# perfect-cell-v0_1.net
KiCad netlist of a schematic drawn in EAGLE
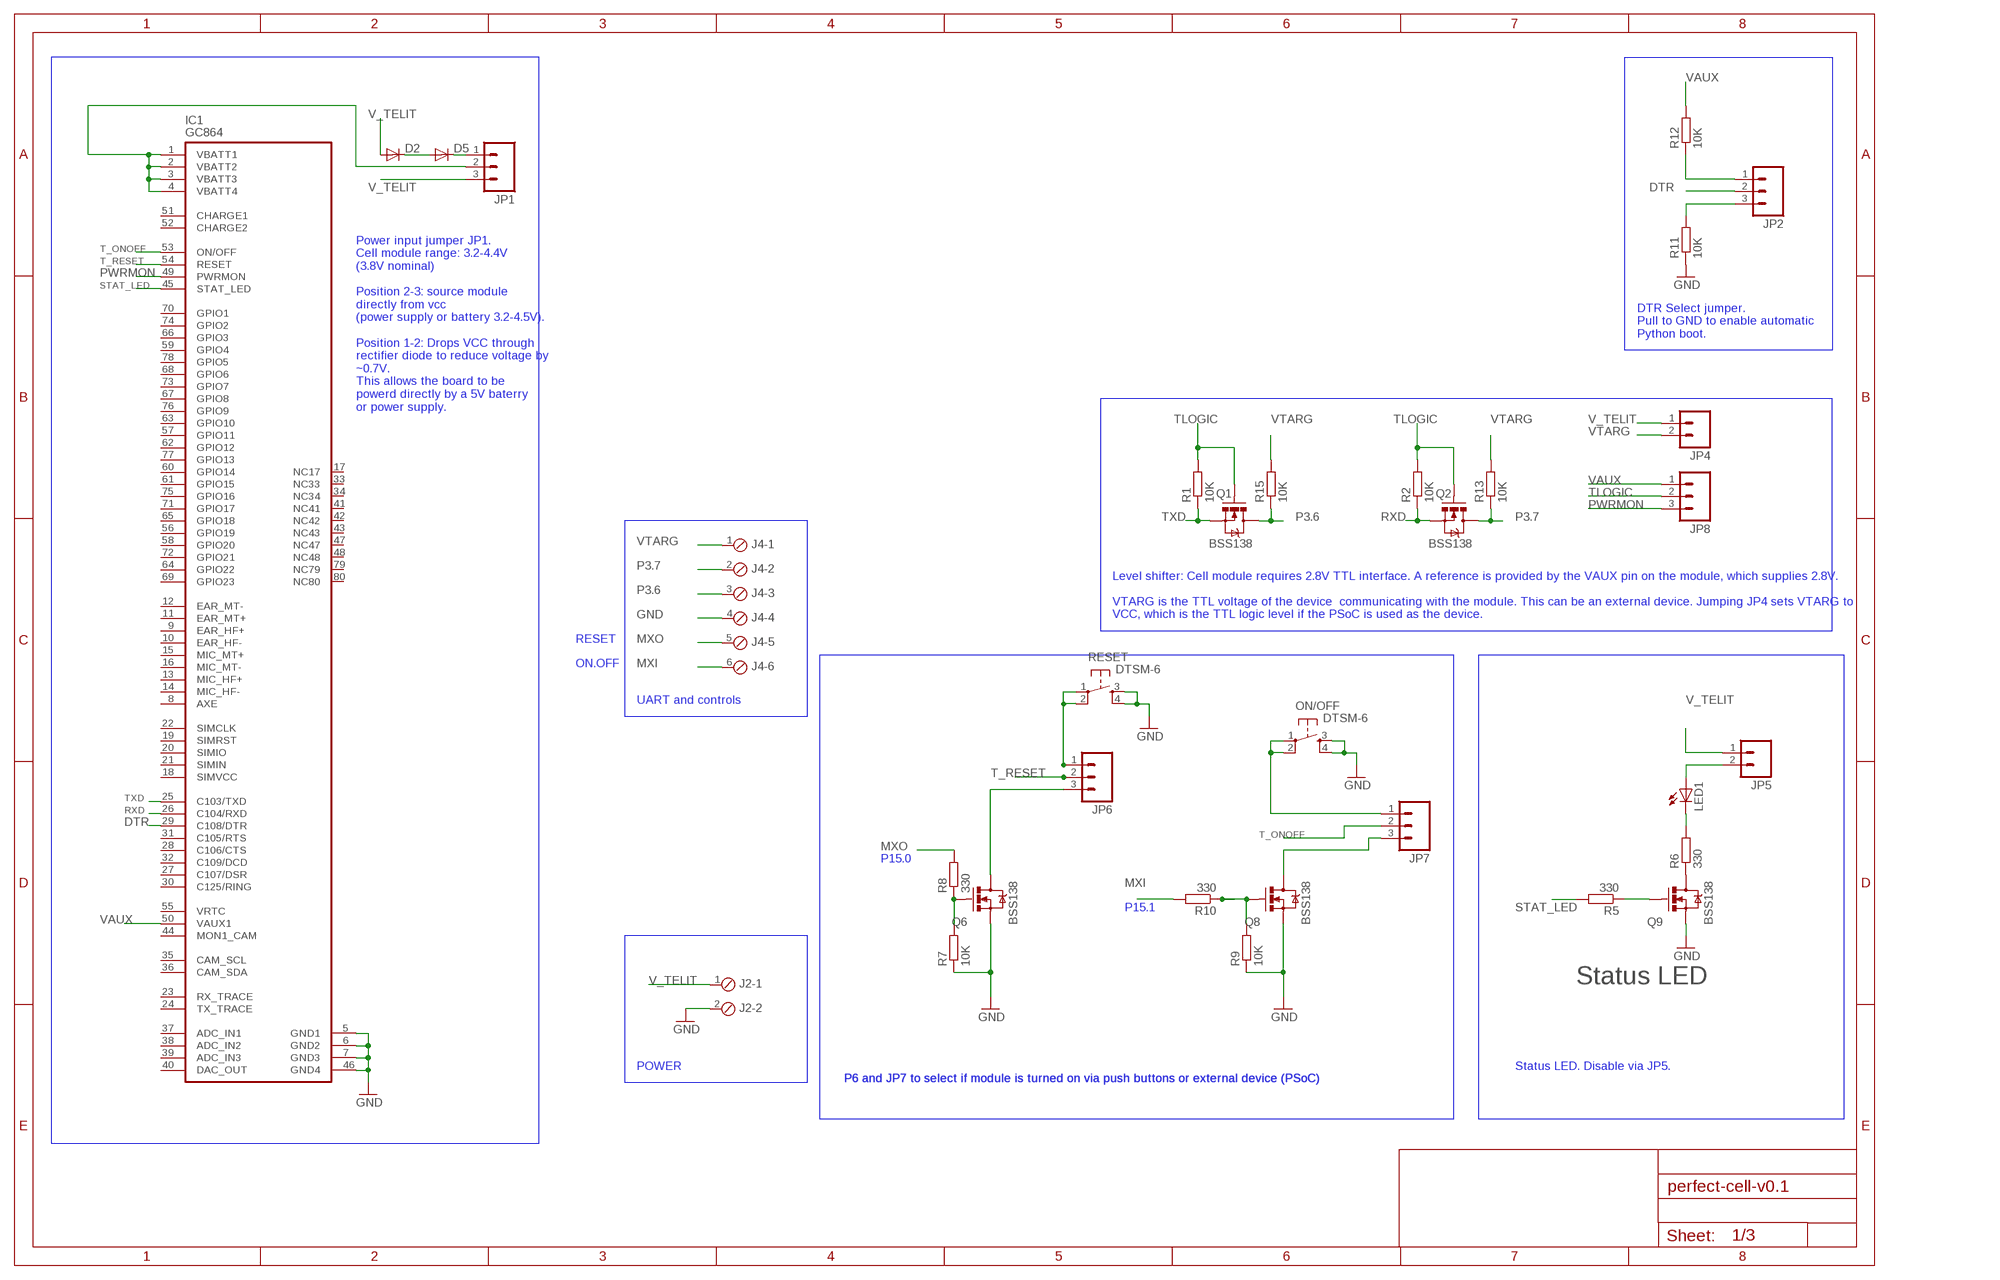
[diagram p0: schematic, sheet 1]
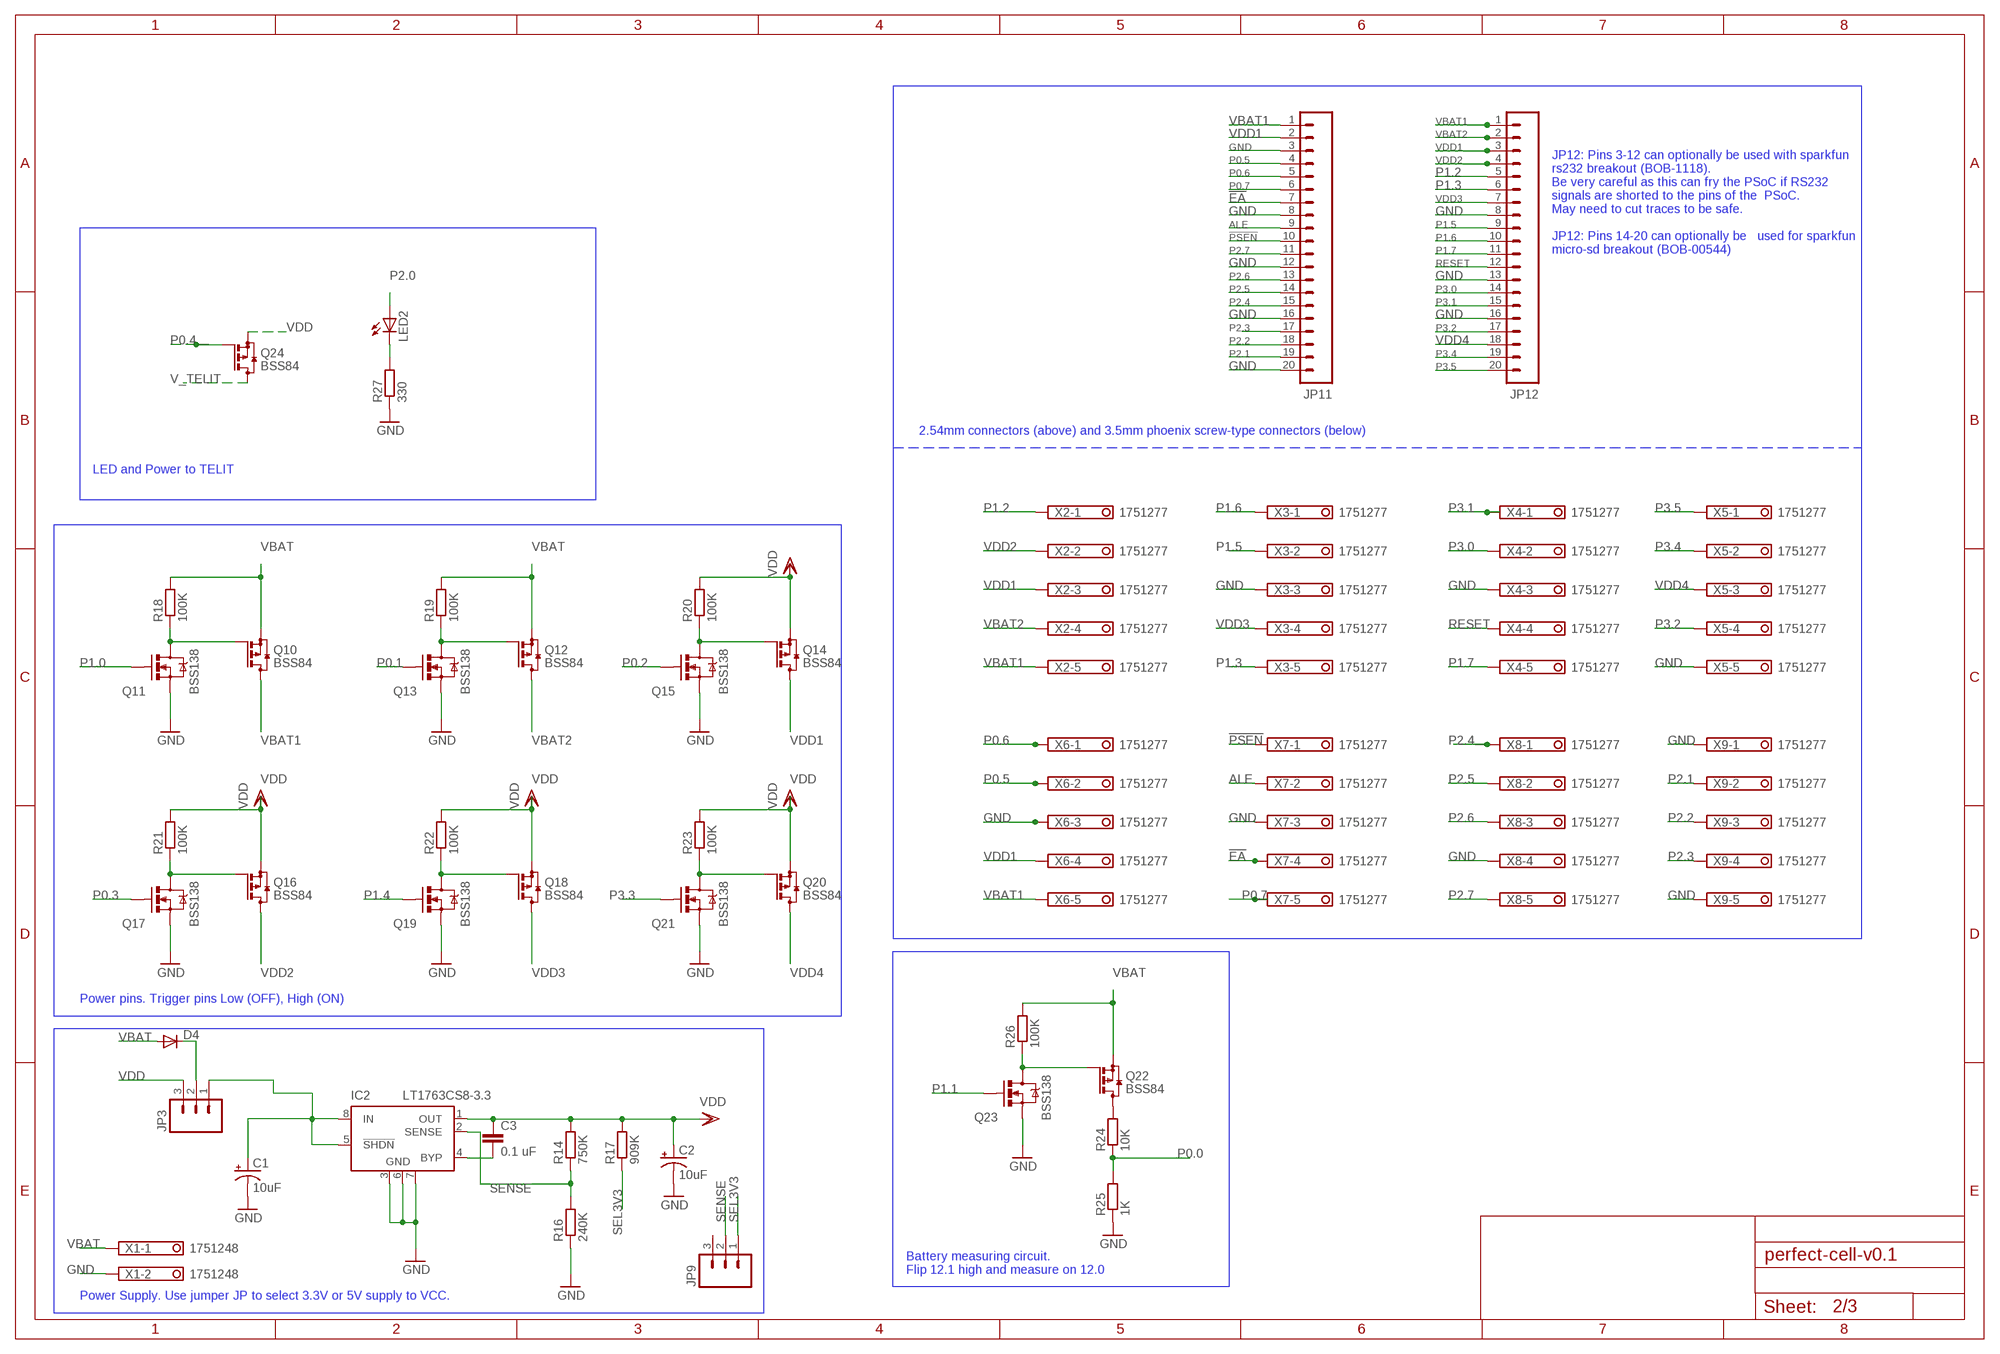
[diagram p1: schematic, sheet 2]
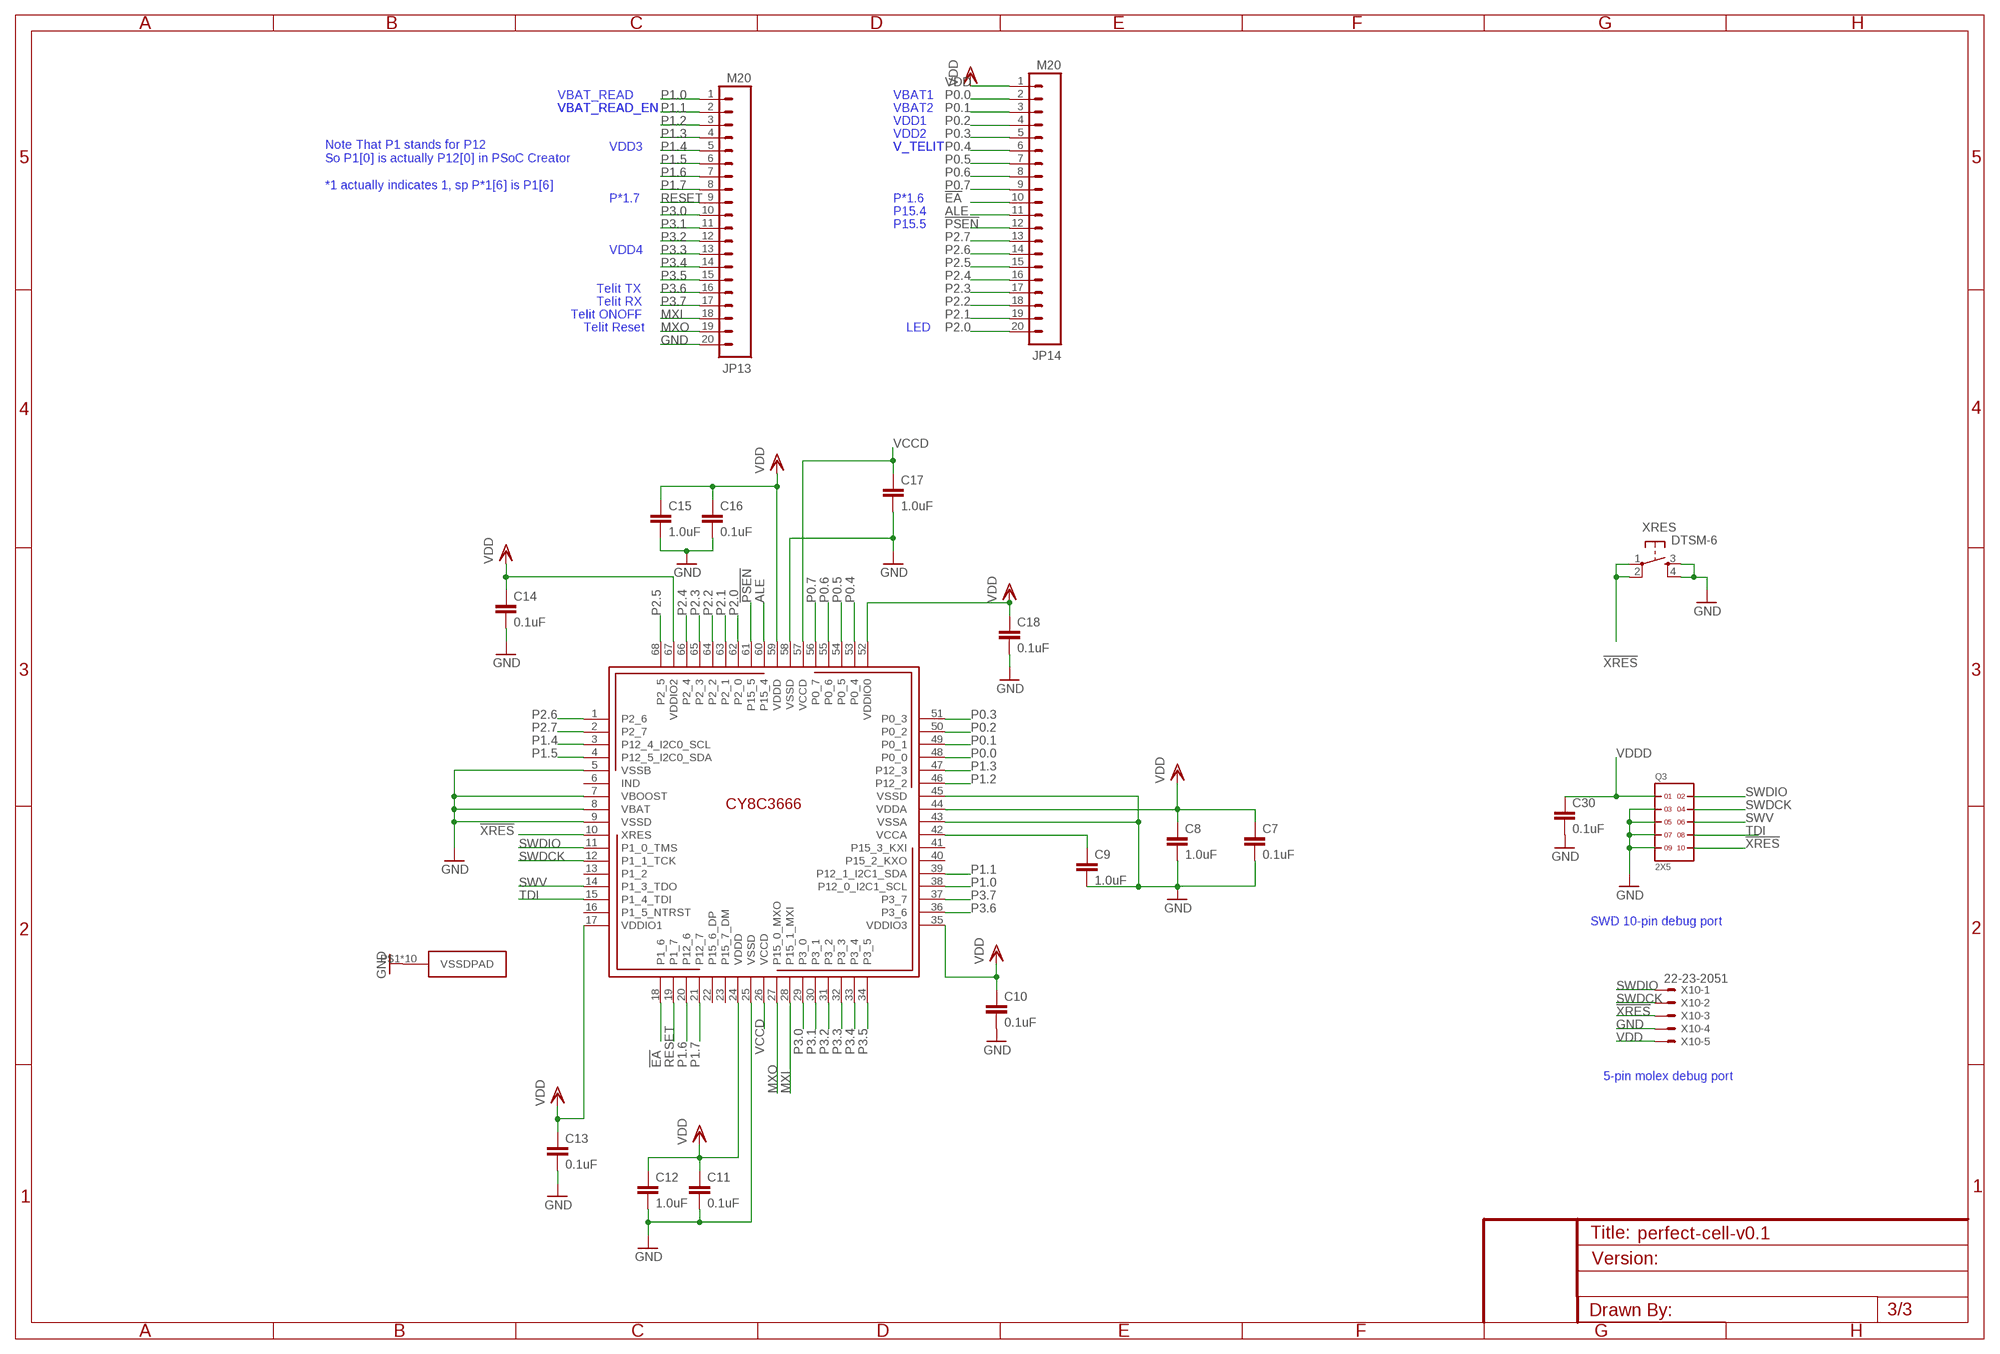
[diagram p2: schematic, sheet 3]

(export (version "E")
  (design (tool "Eeschema 10.0.6"))
  (components
    (comp (ref "C1")
      (value "10uF")
      (footprint "eagle-import:EIA3216")
      (libsource (lib "eagle-import") (part "10UF-16V-10%(TANT)"))
    )
    (comp (ref "C2")
      (value "10uF")
      (footprint "eagle-import:EIA3216")
      (libsource (lib "eagle-import") (part "10UF-16V-10%(TANT)"))
    )
    (comp (ref "C3")
      (value "0.1 uF")
      (footprint "eagle-import:0402-CAP")
      (libsource (lib "eagle-import") (part "CAP0402-CAP"))
    )
    (comp (ref "D4")
      (value "DIODESMA")
      (footprint "eagle-import:SMA-DIODE")
      (libsource (lib "eagle-import") (part "DIODESMA"))
    )
    (comp (ref "IC2")
      (value "LT1763CS8-3.3")
      (footprint "eagle-import:SOIC8")
      (libsource (lib "eagle-import") (part "LT1763CS8-3.3"))
    )
    (comp (ref "JP3")
      (value "M03LOCK")
      (footprint "eagle-import:1X03_LOCK")
      (libsource (lib "eagle-import") (part "M03LOCK"))
    )
    (comp (ref "JP9")
      (value "M03LOCK")
      (footprint "eagle-import:1X03_LOCK")
      (libsource (lib "eagle-import") (part "M03LOCK"))
    )
    (comp (ref "JP11")
      (value "M20")
      (footprint "eagle-import:1X20")
      (libsource (lib "eagle-import") (part "SparkFun-Connectors_M20"))
    )
    (comp (ref "JP12")
      (value "M20")
      (footprint "eagle-import:1X20")
      (libsource (lib "eagle-import") (part "SparkFun-Connectors_M20"))
    )
    (comp (ref "LED2")
      (value "LEDSML0805")
      (footprint "eagle-import:SML0805")
      (libsource (lib "eagle-import") (part "LEDSML0805"))
    )
    (comp (ref "Q10")
      (value "BSS84")
      (footprint "eagle-import:SOT23")
      (libsource (lib "eagle-import") (part "BSS84"))
    )
    (comp (ref "Q11")
      (value "BSS138")
      (footprint "eagle-import:SOT23-3")
      (libsource (lib "eagle-import") (part "MOSFET-NCHANNELSMD"))
    )
    (comp (ref "Q12")
      (value "BSS84")
      (footprint "eagle-import:SOT23")
      (libsource (lib "eagle-import") (part "BSS84"))
    )
    (comp (ref "Q13")
      (value "BSS138")
      (footprint "eagle-import:SOT23-3")
      (libsource (lib "eagle-import") (part "MOSFET-NCHANNELSMD"))
    )
    (comp (ref "Q14")
      (value "BSS84")
      (footprint "eagle-import:SOT23")
      (libsource (lib "eagle-import") (part "BSS84"))
    )
    (comp (ref "Q15")
      (value "BSS138")
      (footprint "eagle-import:SOT23-3")
      (libsource (lib "eagle-import") (part "MOSFET-NCHANNELSMD"))
    )
    (comp (ref "Q16")
      (value "BSS84")
      (footprint "eagle-import:SOT23")
      (libsource (lib "eagle-import") (part "BSS84"))
    )
    (comp (ref "Q17")
      (value "BSS138")
      (footprint "eagle-import:SOT23-3")
      (libsource (lib "eagle-import") (part "MOSFET-NCHANNELSMD"))
    )
    (comp (ref "Q18")
      (value "BSS84")
      (footprint "eagle-import:SOT23")
      (libsource (lib "eagle-import") (part "BSS84"))
    )
    (comp (ref "Q19")
      (value "BSS138")
      (footprint "eagle-import:SOT23-3")
      (libsource (lib "eagle-import") (part "MOSFET-NCHANNELSMD"))
    )
    (comp (ref "Q20")
      (value "BSS84")
      (footprint "eagle-import:SOT23")
      (libsource (lib "eagle-import") (part "BSS84"))
    )
    (comp (ref "Q21")
      (value "BSS138")
      (footprint "eagle-import:SOT23-3")
      (libsource (lib "eagle-import") (part "MOSFET-NCHANNELSMD"))
    )
    (comp (ref "Q22")
      (value "BSS84")
      (footprint "eagle-import:SOT23")
      (libsource (lib "eagle-import") (part "BSS84"))
    )
    (comp (ref "Q23")
      (value "BSS138")
      (footprint "eagle-import:SOT23-3")
      (libsource (lib "eagle-import") (part "MOSFET-NCHANNELSMD"))
    )
    (comp (ref "Q24")
      (value "BSS84")
      (footprint "eagle-import:SOT23")
      (libsource (lib "eagle-import") (part "BSS84"))
    )
    (comp (ref "R14")
      (value "750K")
      (footprint "eagle-import:R0805")
      (libsource (lib "eagle-import") (part "R-EU_R0805"))
    )
    (comp (ref "R16")
      (value "240K")
      (footprint "eagle-import:R0805")
      (libsource (lib "eagle-import") (part "R-EU_R0805"))
    )
    (comp (ref "R17")
      (value "909K")
      (footprint "eagle-import:R0805")
      (libsource (lib "eagle-import") (part "R-EU_R0805"))
    )
    (comp (ref "R18")
      (value "100K")
      (footprint "eagle-import:R0805")
      (libsource (lib "eagle-import") (part "R-EU_R0805"))
    )
    (comp (ref "R19")
      (value "100K")
      (footprint "eagle-import:R0805")
      (libsource (lib "eagle-import") (part "R-EU_R0805"))
    )
    (comp (ref "R20")
      (value "100K")
      (footprint "eagle-import:R0805")
      (libsource (lib "eagle-import") (part "R-EU_R0805"))
    )
    (comp (ref "R21")
      (value "100K")
      (footprint "eagle-import:R0805")
      (libsource (lib "eagle-import") (part "R-EU_R0805"))
    )
    (comp (ref "R22")
      (value "100K")
      (footprint "eagle-import:R0805")
      (libsource (lib "eagle-import") (part "R-EU_R0805"))
    )
    (comp (ref "R23")
      (value "100K")
      (footprint "eagle-import:R0805")
      (libsource (lib "eagle-import") (part "R-EU_R0805"))
    )
    (comp (ref "R24")
      (value "10K")
      (footprint "eagle-import:R0805")
      (libsource (lib "eagle-import") (part "R-EU_R0805"))
    )
    (comp (ref "R25")
      (value "1K")
      (footprint "eagle-import:R0805")
      (libsource (lib "eagle-import") (part "R-EU_R0805"))
    )
    (comp (ref "R26")
      (value "100K")
      (footprint "eagle-import:R0805")
      (libsource (lib "eagle-import") (part "R-EU_R0805"))
    )
    (comp (ref "R27")
      (value "330")
      (footprint "eagle-import:R0805")
      (libsource (lib "eagle-import") (part "R-EU_R0805"))
    )
    (comp (ref "X1")
      (value "1751248")
      (footprint "eagle-import:1751248")
      (libsource (lib "eagle-import") (part "1751248"))
    )
    (comp (ref "X2")
      (value "1751277")
      (footprint "eagle-import:1751277")
      (libsource (lib "eagle-import") (part "1751277"))
    )
    (comp (ref "X3")
      (value "1751277")
      (footprint "eagle-import:1751277")
      (libsource (lib "eagle-import") (part "1751277"))
    )
    (comp (ref "X4")
      (value "1751277")
      (footprint "eagle-import:1751277")
      (libsource (lib "eagle-import") (part "1751277"))
    )
    (comp (ref "X5")
      (value "1751277")
      (footprint "eagle-import:1751277")
      (libsource (lib "eagle-import") (part "1751277"))
    )
    (comp (ref "X6")
      (value "1751277")
      (footprint "eagle-import:1751277")
      (libsource (lib "eagle-import") (part "1751277"))
    )
    (comp (ref "X7")
      (value "1751277")
      (footprint "eagle-import:1751277")
      (libsource (lib "eagle-import") (part "1751277"))
    )
    (comp (ref "X8")
      (value "1751277")
      (footprint "eagle-import:1751277")
      (libsource (lib "eagle-import") (part "1751277"))
    )
    (comp (ref "X9")
      (value "1751277")
      (footprint "eagle-import:1751277")
      (libsource (lib "eagle-import") (part "1751277"))
    )
    (comp (ref "C7")
      (value "0.1uF")
      (footprint "eagle-import:0402-CAP")
      (libsource (lib "eagle-import") (part "CAP0402-CAP"))
    )
    (comp (ref "C8")
      (value "1.0uF")
      (footprint "eagle-import:0402-CAP")
      (libsource (lib "eagle-import") (part "CAP0402-CAP"))
    )
    (comp (ref "C9")
      (value "1.0uF")
      (footprint "eagle-import:0402-CAP")
      (libsource (lib "eagle-import") (part "CAP0402-CAP"))
    )
    (comp (ref "C10")
      (value "0.1uF")
      (footprint "eagle-import:0402-CAP")
      (libsource (lib "eagle-import") (part "CAP0402-CAP"))
    )
    (comp (ref "C11")
      (value "0.1uF")
      (footprint "eagle-import:0402-CAP")
      (libsource (lib "eagle-import") (part "CAP0402-CAP"))
    )
    (comp (ref "C12")
      (value "1.0uF")
      (footprint "eagle-import:0402-CAP")
      (libsource (lib "eagle-import") (part "CAP0402-CAP"))
    )
    (comp (ref "C13")
      (value "0.1uF")
      (footprint "eagle-import:0402-CAP")
      (libsource (lib "eagle-import") (part "CAP0402-CAP"))
    )
    (comp (ref "C14")
      (value "0.1uF")
      (footprint "eagle-import:0402-CAP")
      (libsource (lib "eagle-import") (part "CAP0402-CAP"))
    )
    (comp (ref "C15")
      (value "1.0uF")
      (footprint "eagle-import:0402-CAP")
      (libsource (lib "eagle-import") (part "CAP0402-CAP"))
    )
    (comp (ref "C16")
      (value "0.1uF")
      (footprint "eagle-import:0402-CAP")
      (libsource (lib "eagle-import") (part "CAP0402-CAP"))
    )
    (comp (ref "C17")
      (value "1.0uF")
      (footprint "eagle-import:0402-CAP")
      (libsource (lib "eagle-import") (part "CAP0402-CAP"))
    )
    (comp (ref "C18")
      (value "0.1uF")
      (footprint "eagle-import:0402-CAP")
      (libsource (lib "eagle-import") (part "CAP0402-CAP"))
    )
    (comp (ref "C30")
      (value "0.1uF")
      (footprint "eagle-import:0402-CAP")
      (libsource (lib "eagle-import") (part "CAP0402-CAP"))
    )
    (comp (ref "JP13")
      (value "M20")
      (footprint "eagle-import:1X20")
      (libsource (lib "eagle-import") (part "M20"))
    )
    (comp (ref "JP14")
      (value "M20")
      (footprint "eagle-import:1X20")
      (libsource (lib "eagle-import") (part "M20"))
    )
    (comp (ref "Q3")
      (value "2X5")
      (footprint "eagle-import:FTSH-105-01-XXX-DV-K")
      (libsource (lib "eagle-import") (part "2X5"))
    )
    (comp (ref "U$1")
      (value "CY8C3X66LTI")
      (footprint "eagle-import:QFN-68")
      (fields (field (name "PN") "CY8C5568LTI-114"))
      (libsource (lib "eagle-import") (part "CY8C3X66LTI"))
    )
    (comp (ref "X10")
      (value "22-23-2051")
      (footprint "eagle-import:22-23-2051")
      (fields (field (name "MF") "MOLEX"))
      (libsource (lib "eagle-import") (part "22-23-2051"))
    )
    (comp (ref "XRES")
      (value "DTSM-6")
      (footprint "eagle-import:DTSM-6")
      (libsource (lib "eagle-import") (part "DTSM-6"))
    )
    (comp (ref "D2")
      (value "DIODESMA")
      (footprint "eagle-import:SMA-DIODE")
      (libsource (lib "eagle-import") (part "DIODESMA"))
    )
    (comp (ref "D5")
      (value "DIODESMA")
      (footprint "eagle-import:SMA-DIODE")
      (libsource (lib "eagle-import") (part "DIODESMA"))
    )
    (comp (ref "IC1")
      (value "GC864")
      (footprint "eagle-import:GC864")
      (libsource (lib "eagle-import") (part "GC864"))
    )
    (comp (ref "J2")
      (value "MPT2")
      (footprint "eagle-import:2POL254")
      (libsource (lib "eagle-import") (part "MPT2"))
    )
    (comp (ref "J4")
      (value "MPT6")
      (footprint "eagle-import:6POL254")
      (libsource (lib "eagle-import") (part "MPT6"))
    )
    (comp (ref "JP1")
      (value "M03LOCK")
      (footprint "eagle-import:1X03_LOCK")
      (libsource (lib "eagle-import") (part "M03LOCK"))
    )
    (comp (ref "JP2")
      (value "M03LOCK")
      (footprint "eagle-import:1X03_LOCK")
      (libsource (lib "eagle-import") (part "M03LOCK"))
    )
    (comp (ref "JP4")
      (value "M02LOCK")
      (footprint "eagle-import:1X02_LOCK")
      (libsource (lib "eagle-import") (part "M02LOCK"))
    )
    (comp (ref "JP5")
      (value "M02LOCK")
      (footprint "eagle-import:1X02_LOCK")
      (libsource (lib "eagle-import") (part "M02LOCK"))
    )
    (comp (ref "JP6")
      (value "M03LOCK")
      (footprint "eagle-import:1X03_LOCK")
      (libsource (lib "eagle-import") (part "M03LOCK"))
    )
    (comp (ref "JP7")
      (value "M03LOCK")
      (footprint "eagle-import:1X03_LOCK")
      (libsource (lib "eagle-import") (part "M03LOCK"))
    )
    (comp (ref "JP8")
      (value "M03LOCK")
      (footprint "eagle-import:1X03_LOCK")
      (libsource (lib "eagle-import") (part "M03LOCK"))
    )
    (comp (ref "LED1")
      (value "LEDSML0805")
      (footprint "eagle-import:SML0805")
      (libsource (lib "eagle-import") (part "LEDSML0805"))
    )
    (comp (ref "ON/OFF")
      (value "DTSM-6")
      (footprint "eagle-import:DTSM-6")
      (libsource (lib "eagle-import") (part "DTSM-6"))
    )
    (comp (ref "Q1")
      (value "BSS138")
      (footprint "eagle-import:SOT23-3")
      (libsource (lib "eagle-import") (part "MOSFET-NCHANNELSMD"))
    )
    (comp (ref "Q2")
      (value "BSS138")
      (footprint "eagle-import:SOT23-3")
      (libsource (lib "eagle-import") (part "MOSFET-NCHANNELSMD"))
    )
    (comp (ref "Q6")
      (value "BSS138")
      (footprint "eagle-import:SOT23-3")
      (libsource (lib "eagle-import") (part "MOSFET-NCHANNELSMD"))
    )
    (comp (ref "Q8")
      (value "BSS138")
      (footprint "eagle-import:SOT23-3")
      (libsource (lib "eagle-import") (part "MOSFET-NCHANNELSMD"))
    )
    (comp (ref "Q9")
      (value "BSS138")
      (footprint "eagle-import:SOT23-3")
      (libsource (lib "eagle-import") (part "MOSFET-NCHANNELSMD"))
    )
    (comp (ref "R1")
      (value "10K")
      (footprint "eagle-import:R0805")
      (libsource (lib "eagle-import") (part "R-EU_R0805"))
    )
    (comp (ref "R2")
      (value "10K")
      (footprint "eagle-import:R0805")
      (libsource (lib "eagle-import") (part "R-EU_R0805"))
    )
    (comp (ref "R5")
      (value "330")
      (footprint "eagle-import:R0805")
      (libsource (lib "eagle-import") (part "R-EU_R0805"))
    )
    (comp (ref "R6")
      (value "330")
      (footprint "eagle-import:R0805")
      (libsource (lib "eagle-import") (part "R-EU_R0805"))
    )
    (comp (ref "R7")
      (value "10K")
      (footprint "eagle-import:R0805")
      (libsource (lib "eagle-import") (part "R-EU_R0805"))
    )
    (comp (ref "R8")
      (value "330")
      (footprint "eagle-import:R0805")
      (libsource (lib "eagle-import") (part "R-EU_R0805"))
    )
    (comp (ref "R9")
      (value "10K")
      (footprint "eagle-import:R0805")
      (libsource (lib "eagle-import") (part "R-EU_R0805"))
    )
    (comp (ref "R10")
      (value "330")
      (footprint "eagle-import:R0805")
      (libsource (lib "eagle-import") (part "R-EU_R0805"))
    )
    (comp (ref "R11")
      (value "10K")
      (footprint "eagle-import:R0805")
      (libsource (lib "eagle-import") (part "R-EU_R0805"))
    )
    (comp (ref "R12")
      (value "10K")
      (footprint "eagle-import:R0805")
      (libsource (lib "eagle-import") (part "R-EU_R0805"))
    )
    (comp (ref "R13")
      (value "10K")
      (footprint "eagle-import:R0805")
      (libsource (lib "eagle-import") (part "R-EU_R0805"))
    )
    (comp (ref "R15")
      (value "10K")
      (footprint "eagle-import:R0805")
      (libsource (lib "eagle-import") (part "R-EU_R0805"))
    )
    (comp (ref "RESET")
      (value "DTSM-6")
      (footprint "eagle-import:DTSM-6")
      (libsource (lib "eagle-import") (part "DTSM-6"))
    )
  )
  (nets
    (net (code "1") (name "ALE") (class "Default")
      (node (ref "JP11") (pin "9") (pinfunction "9_9") (pintype "passive"))
      (node (ref "JP14") (pin "11") (pinfunction "11_11") (pintype "passive"))
      (node (ref "U$1") (pin "60") (pinfunction "P15_4_60") (pintype "passive"))
      (node (ref "X7") (pin "2") (pinfunction "K_2") (pintype "passive"))
    )
    (net (code "2") (name "CHARGE1") (class "Default")
      (node (ref "IC1") (pin "51") (pinfunction "CHARGE1_51") (pintype "power_in"))
    )
    (net (code "3") (name "CHARGE2") (class "Default")
      (node (ref "IC1") (pin "52") (pinfunction "CHARGE2_52") (pintype "power_in"))
    )
    (net (code "4") (name "DTR") (class "Default")
      (node (ref "IC1") (pin "29") (pinfunction "C108/DTR_29") (pintype "input"))
      (node (ref "JP2") (pin "2") (pinfunction "2_2") (pintype "passive"))
    )
    (net (code "5") (name "GND") (class "Default")
      (node (ref "C1") (pin "C") (pinfunction "-_C") (pintype "passive"))
      (node (ref "C10") (pin "2") (pinfunction "2_2") (pintype "passive"))
      (node (ref "C11") (pin "2") (pinfunction "2_2") (pintype "passive"))
      (node (ref "C12") (pin "2") (pinfunction "2_2") (pintype "passive"))
      (node (ref "C13") (pin "2") (pinfunction "2_2") (pintype "passive"))
      (node (ref "C14") (pin "2") (pinfunction "2_2") (pintype "passive"))
      (node (ref "C15") (pin "2") (pinfunction "2_2") (pintype "passive"))
      (node (ref "C16") (pin "2") (pinfunction "2_2") (pintype "passive"))
      (node (ref "C17") (pin "2") (pinfunction "2_2") (pintype "passive"))
      (node (ref "C18") (pin "2") (pinfunction "2_2") (pintype "passive"))
      (node (ref "C2") (pin "C") (pinfunction "-_C") (pintype "passive"))
      (node (ref "C30") (pin "2") (pinfunction "2_2") (pintype "passive"))
      (node (ref "C7") (pin "2") (pinfunction "2_2") (pintype "passive"))
      (node (ref "C8") (pin "2") (pinfunction "2_2") (pintype "passive"))
      (node (ref "C9") (pin "2") (pinfunction "2_2") (pintype "passive"))
      (node (ref "IC1") (pin "46") (pinfunction "GND4_46") (pintype "power_in"))
      (node (ref "IC1") (pin "5") (pinfunction "GND1_5") (pintype "power_in"))
      (node (ref "IC1") (pin "6") (pinfunction "GND2_6") (pintype "power_in"))
      (node (ref "IC1") (pin "7") (pinfunction "GND3_7") (pintype "power_in"))
      (node (ref "IC2") (pin "3") (pinfunction "GND_3") (pintype "power_in"))
      (node (ref "IC2") (pin "6") (pinfunction "GND_6") (pintype "power_in"))
      (node (ref "IC2") (pin "7") (pinfunction "GND_7") (pintype "power_in"))
      (node (ref "J2") (pin "2") (pinfunction "1_2") (pintype "passive"))
      (node (ref "J4") (pin "4") (pinfunction "1_4") (pintype "passive"))
      (node (ref "JP11") (pin "12") (pinfunction "12_12") (pintype "passive"))
      (node (ref "JP11") (pin "16") (pinfunction "16_16") (pintype "passive"))
      (node (ref "JP11") (pin "20") (pinfunction "20_20") (pintype "passive"))
      (node (ref "JP11") (pin "3") (pinfunction "3_3") (pintype "passive"))
      (node (ref "JP11") (pin "8") (pinfunction "8_8") (pintype "passive"))
      (node (ref "JP12") (pin "13") (pinfunction "13_13") (pintype "passive"))
      (node (ref "JP12") (pin "16") (pinfunction "16_16") (pintype "passive"))
      (node (ref "JP12") (pin "8") (pinfunction "8_8") (pintype "passive"))
      (node (ref "JP13") (pin "20") (pinfunction "20_20") (pintype "passive"))
      (node (ref "ON/OFF") (pin "3") (pinfunction "3_3") (pintype "passive"))
      (node (ref "ON/OFF") (pin "4") (pinfunction "4_4") (pintype "passive"))
      (node (ref "Q11") (pin "2") (pinfunction "S_2") (pintype "passive"))
      (node (ref "Q13") (pin "2") (pinfunction "S_2") (pintype "passive"))
      (node (ref "Q15") (pin "2") (pinfunction "S_2") (pintype "passive"))
      (node (ref "Q17") (pin "2") (pinfunction "S_2") (pintype "passive"))
      (node (ref "Q19") (pin "2") (pinfunction "S_2") (pintype "passive"))
      (node (ref "Q21") (pin "2") (pinfunction "S_2") (pintype "passive"))
      (node (ref "Q23") (pin "2") (pinfunction "S_2") (pintype "passive"))
      (node (ref "Q3") (pin "3") (pinfunction "3_3") (pintype "bidirectional"))
      (node (ref "Q3") (pin "5") (pinfunction "5_5") (pintype "bidirectional"))
      (node (ref "Q3") (pin "7") (pinfunction "7_7") (pintype "bidirectional"))
      (node (ref "Q3") (pin "9") (pinfunction "9_9") (pintype "bidirectional"))
      (node (ref "Q6") (pin "2") (pinfunction "S_2") (pintype "passive"))
      (node (ref "Q8") (pin "2") (pinfunction "S_2") (pintype "passive"))
      (node (ref "Q9") (pin "2") (pinfunction "S_2") (pintype "passive"))
      (node (ref "R11") (pin "1") (pinfunction "1_1") (pintype "passive"))
      (node (ref "R16") (pin "1") (pinfunction "1_1") (pintype "passive"))
      (node (ref "R25") (pin "1") (pinfunction "1_1") (pintype "passive"))
      (node (ref "R27") (pin "1") (pinfunction "1_1") (pintype "passive"))
      (node (ref "R7") (pin "1") (pinfunction "1_1") (pintype "passive"))
      (node (ref "R9") (pin "1") (pinfunction "1_1") (pintype "passive"))
      (node (ref "RESET") (pin "3") (pinfunction "3_3") (pintype "passive"))
      (node (ref "RESET") (pin "4") (pinfunction "4_4") (pintype "passive"))
      (node (ref "U$1") (pin "25") (pinfunction "VSSD_25") (pintype "passive"))
      (node (ref "U$1") (pin "43") (pinfunction "VSSA_43") (pintype "passive"))
      (node (ref "U$1") (pin "45") (pinfunction "VSSD_45") (pintype "passive"))
      (node (ref "U$1") (pin "5") (pinfunction "VSSB_5") (pintype "passive"))
      (node (ref "U$1") (pin "58") (pinfunction "VSSD_58") (pintype "passive"))
      (node (ref "U$1") (pin "7") (pinfunction "VBOOST_7") (pintype "passive"))
      (node (ref "U$1") (pin "8") (pinfunction "VBAT_8") (pintype "passive"))
      (node (ref "U$1") (pin "9") (pinfunction "VSSD_9") (pintype "passive"))
      (node (ref "U$1") (pin "P$1") (pinfunction "VSSDPAD_P$1") (pintype "power_in"))
      (node (ref "U$1") (pin "P$2") (pinfunction "VSSDPAD_P$2") (pintype "power_in"))
      (node (ref "U$1") (pin "P$3") (pinfunction "VSSDPAD_P$3") (pintype "power_in"))
      (node (ref "U$1") (pin "P$4") (pinfunction "VSSDPAD_P$4") (pintype "power_in"))
      (node (ref "U$1") (pin "P$5") (pinfunction "VSSDPAD_P$5") (pintype "power_in"))
      (node (ref "U$1") (pin "P$6") (pinfunction "VSSDPAD_P$6") (pintype "power_in"))
      (node (ref "U$1") (pin "P$7") (pinfunction "VSSDPAD_P$7") (pintype "power_in"))
      (node (ref "U$1") (pin "P$8") (pinfunction "VSSDPAD_P$8") (pintype "power_in"))
      (node (ref "U$1") (pin "P$9") (pinfunction "VSSDPAD_P$9") (pintype "power_in"))
      (node (ref "U$1") (pin "PAD") (pinfunction "VSSDPAD_PAD") (pintype "power_in"))
      (node (ref "X1") (pin "2") (pinfunction "K_2") (pintype "passive"))
      (node (ref "X10") (pin "4") (pinfunction "S_4") (pintype "passive"))
      (node (ref "X3") (pin "3") (pinfunction "K_3") (pintype "passive"))
      (node (ref "X4") (pin "3") (pinfunction "K_3") (pintype "passive"))
      (node (ref "X5") (pin "5") (pinfunction "K_5") (pintype "passive"))
      (node (ref "X6") (pin "3") (pinfunction "K_3") (pintype "passive"))
      (node (ref "X7") (pin "3") (pinfunction "K_3") (pintype "passive"))
      (node (ref "X8") (pin "4") (pinfunction "K_4") (pintype "passive"))
      (node (ref "X9") (pin "1") (pinfunction "K_1") (pintype "passive"))
      (node (ref "X9") (pin "5") (pinfunction "K_5") (pintype "passive"))
      (node (ref "XRES") (pin "3") (pinfunction "3_3") (pintype "passive"))
      (node (ref "XRES") (pin "4") (pinfunction "4_4") (pintype "passive"))
    )
    (net (code "6") (name "MXI") (class "Default")
      (node (ref "J4") (pin "6") (pinfunction "1_6") (pintype "passive"))
      (node (ref "JP13") (pin "18") (pinfunction "18_18") (pintype "passive"))
      (node (ref "R10") (pin "2") (pinfunction "2_2") (pintype "passive"))
      (node (ref "U$1") (pin "28") (pinfunction "P15_1_MXI_28") (pintype "passive"))
    )
    (net (code "7") (name "MXO") (class "Default")
      (node (ref "J4") (pin "5") (pinfunction "1_5") (pintype "passive"))
      (node (ref "JP13") (pin "19") (pinfunction "19_19") (pintype "passive"))
      (node (ref "R8") (pin "2") (pinfunction "2_2") (pintype "passive"))
      (node (ref "U$1") (pin "27") (pinfunction "P15_0_MXO_27") (pintype "passive"))
    )
    (net (code "8") (name "Net-(C1-+)") (class "Default")
      (node (ref "C1") (pin "A") (pinfunction "+_A") (pintype "passive"))
      (node (ref "IC2") (pin "5") (pinfunction "~{SHDN}_5") (pintype "input"))
      (node (ref "IC2") (pin "8") (pinfunction "IN_8") (pintype "input"))
      (node (ref "JP3") (pin "1") (pinfunction "1_1") (pintype "passive"))
    )
    (net (code "9") (name "Net-(D2-PadC)") (class "Default")
      (node (ref "D2") (pin "C") (pinfunction "C_C") (pintype "passive"))
      (node (ref "D5") (pin "A") (pinfunction "A_A") (pintype "passive"))
    )
    (net (code "10") (name "Net-(D4-PadC)") (class "Default")
      (node (ref "D4") (pin "C") (pinfunction "C_C") (pintype "passive"))
      (node (ref "JP3") (pin "2") (pinfunction "2_2") (pintype "passive"))
    )
    (net (code "11") (name "Net-(D5-PadC)") (class "Default")
      (node (ref "D5") (pin "C") (pinfunction "C_C") (pintype "passive"))
      (node (ref "JP1") (pin "1") (pinfunction "1_1") (pintype "passive"))
    )
    (net (code "12") (name "Net-(IC1-VBATT1)") (class "Default")
      (node (ref "IC1") (pin "1") (pinfunction "VBATT1_1") (pintype "power_in"))
      (node (ref "IC1") (pin "2") (pinfunction "VBATT2_2") (pintype "power_in"))
      (node (ref "IC1") (pin "3") (pinfunction "VBATT3_3") (pintype "power_in"))
      (node (ref "IC1") (pin "4") (pinfunction "VBATT4_4") (pintype "power_in"))
      (node (ref "JP1") (pin "2") (pinfunction "2_2") (pintype "passive"))
    )
    (net (code "13") (name "Net-(IC2-BYP)") (class "Default")
      (node (ref "C3") (pin "2") (pinfunction "2_2") (pintype "passive"))
      (node (ref "IC2") (pin "4") (pinfunction "BYP_4") (pintype "input"))
    )
    (net (code "14") (name "Net-(JP2-Pad1)") (class "Default")
      (node (ref "JP2") (pin "1") (pinfunction "1_1") (pintype "passive"))
      (node (ref "R12") (pin "1") (pinfunction "1_1") (pintype "passive"))
    )
    (net (code "15") (name "Net-(JP2-Pad3)") (class "Default")
      (node (ref "JP2") (pin "3") (pinfunction "3_3") (pintype "passive"))
      (node (ref "R11") (pin "2") (pinfunction "2_2") (pintype "passive"))
    )
    (net (code "16") (name "Net-(JP5-Pad2)") (class "Default")
      (node (ref "JP5") (pin "2") (pinfunction "2_2") (pintype "passive"))
      (node (ref "LED1") (pin "A") (pinfunction "A_A") (pintype "passive"))
    )
    (net (code "17") (name "Net-(JP6-Pad1)") (class "Default")
      (node (ref "JP6") (pin "1") (pinfunction "1_1") (pintype "passive"))
      (node (ref "RESET") (pin "1") (pinfunction "1_1") (pintype "passive"))
      (node (ref "RESET") (pin "2") (pinfunction "2_2") (pintype "passive"))
    )
    (net (code "18") (name "Net-(JP7-Pad1)") (class "Default")
      (node (ref "JP7") (pin "1") (pinfunction "1_1") (pintype "passive"))
      (node (ref "ON/OFF") (pin "1") (pinfunction "1_1") (pintype "passive"))
      (node (ref "ON/OFF") (pin "2") (pinfunction "2_2") (pintype "passive"))
    )
    (net (code "19") (name "Net-(LED1-PadC)") (class "Default")
      (node (ref "LED1") (pin "C") (pinfunction "C_C") (pintype "passive"))
      (node (ref "R6") (pin "2") (pinfunction "2_2") (pintype "passive"))
    )
    (net (code "20") (name "Net-(LED2-PadC)") (class "Default")
      (node (ref "LED2") (pin "C") (pinfunction "C_C") (pintype "passive"))
      (node (ref "R27") (pin "2") (pinfunction "2_2") (pintype "passive"))
    )
    (net (code "21") (name "Net-(Q6-D)") (class "Default")
      (node (ref "JP6") (pin "3") (pinfunction "3_3") (pintype "passive"))
      (node (ref "Q6") (pin "3") (pinfunction "D_3") (pintype "passive"))
    )
    (net (code "22") (name "Net-(Q6-G)") (class "Default")
      (node (ref "Q6") (pin "1") (pinfunction "G_1") (pintype "passive"))
      (node (ref "R7") (pin "2") (pinfunction "2_2") (pintype "passive"))
      (node (ref "R8") (pin "1") (pinfunction "1_1") (pintype "passive"))
    )
    (net (code "23") (name "Net-(Q8-D)") (class "Default")
      (node (ref "JP7") (pin "3") (pinfunction "3_3") (pintype "passive"))
      (node (ref "Q8") (pin "3") (pinfunction "D_3") (pintype "passive"))
    )
    (net (code "24") (name "Net-(Q8-G)") (class "Default")
      (node (ref "Q8") (pin "1") (pinfunction "G_1") (pintype "passive"))
      (node (ref "R10") (pin "1") (pinfunction "1_1") (pintype "passive"))
      (node (ref "R9") (pin "2") (pinfunction "2_2") (pintype "passive"))
    )
    (net (code "25") (name "Net-(Q9-D)") (class "Default")
      (node (ref "Q9") (pin "3") (pinfunction "D_3") (pintype "passive"))
      (node (ref "R6") (pin "1") (pinfunction "1_1") (pintype "passive"))
    )
    (net (code "26") (name "Net-(Q9-G)") (class "Default")
      (node (ref "Q9") (pin "1") (pinfunction "G_1") (pintype "passive"))
      (node (ref "R5") (pin "1") (pinfunction "1_1") (pintype "passive"))
    )
    (net (code "27") (name "Net-(Q10-G)") (class "Default")
      (node (ref "Q10") (pin "1") (pinfunction "G_1") (pintype "passive"))
      (node (ref "Q11") (pin "3") (pinfunction "D_3") (pintype "passive"))
      (node (ref "R18") (pin "1") (pinfunction "1_1") (pintype "passive"))
    )
    (net (code "28") (name "Net-(Q12-G)") (class "Default")
      (node (ref "Q12") (pin "1") (pinfunction "G_1") (pintype "passive"))
      (node (ref "Q13") (pin "3") (pinfunction "D_3") (pintype "passive"))
      (node (ref "R19") (pin "1") (pinfunction "1_1") (pintype "passive"))
    )
    (net (code "29") (name "Net-(Q14-G)") (class "Default")
      (node (ref "Q14") (pin "1") (pinfunction "G_1") (pintype "passive"))
      (node (ref "Q15") (pin "3") (pinfunction "D_3") (pintype "passive"))
      (node (ref "R20") (pin "1") (pinfunction "1_1") (pintype "passive"))
    )
    (net (code "30") (name "Net-(Q16-G)") (class "Default")
      (node (ref "Q16") (pin "1") (pinfunction "G_1") (pintype "passive"))
      (node (ref "Q17") (pin "3") (pinfunction "D_3") (pintype "passive"))
      (node (ref "R21") (pin "1") (pinfunction "1_1") (pintype "passive"))
    )
    (net (code "31") (name "Net-(Q18-G)") (class "Default")
      (node (ref "Q18") (pin "1") (pinfunction "G_1") (pintype "passive"))
      (node (ref "Q19") (pin "3") (pinfunction "D_3") (pintype "passive"))
      (node (ref "R22") (pin "1") (pinfunction "1_1") (pintype "passive"))
    )
    (net (code "32") (name "Net-(Q20-G)") (class "Default")
      (node (ref "Q20") (pin "1") (pinfunction "G_1") (pintype "passive"))
      (node (ref "Q21") (pin "3") (pinfunction "D_3") (pintype "passive"))
      (node (ref "R23") (pin "1") (pinfunction "1_1") (pintype "passive"))
    )
    (net (code "33") (name "Net-(Q22-D)") (class "Default")
      (node (ref "Q22") (pin "3") (pinfunction "D_3") (pintype "passive"))
      (node (ref "R24") (pin "2") (pinfunction "2_2") (pintype "passive"))
    )
    (net (code "34") (name "Net-(Q22-G)") (class "Default")
      (node (ref "Q22") (pin "1") (pinfunction "G_1") (pintype "passive"))
      (node (ref "Q23") (pin "3") (pinfunction "D_3") (pintype "passive"))
      (node (ref "R26") (pin "1") (pinfunction "1_1") (pintype "passive"))
    )
    (net (code "35") (name "Net-(U$1A-VCCA)") (class "Default")
      (node (ref "C9") (pin "1") (pinfunction "1_1") (pintype "passive"))
      (node (ref "U$1") (pin "42") (pinfunction "VCCA_42") (pintype "passive"))
    )
    (net (code "36") (name "P0.0") (class "Default")
      (node (ref "JP14") (pin "2") (pinfunction "2_2") (pintype "passive"))
      (node (ref "R24") (pin "1") (pinfunction "1_1") (pintype "passive"))
      (node (ref "R25") (pin "2") (pinfunction "2_2") (pintype "passive"))
      (node (ref "U$1") (pin "48") (pinfunction "P0_0_48") (pintype "passive"))
    )
    (net (code "37") (name "P0.1") (class "Default")
      (node (ref "JP14") (pin "3") (pinfunction "3_3") (pintype "passive"))
      (node (ref "Q13") (pin "1") (pinfunction "G_1") (pintype "passive"))
      (node (ref "U$1") (pin "49") (pinfunction "P0_1_49") (pintype "passive"))
    )
    (net (code "38") (name "P0.2") (class "Default")
      (node (ref "JP14") (pin "4") (pinfunction "4_4") (pintype "passive"))
      (node (ref "Q15") (pin "1") (pinfunction "G_1") (pintype "passive"))
      (node (ref "U$1") (pin "50") (pinfunction "P0_2_50") (pintype "passive"))
    )
    (net (code "39") (name "P0.3") (class "Default")
      (node (ref "JP14") (pin "5") (pinfunction "5_5") (pintype "passive"))
      (node (ref "Q17") (pin "1") (pinfunction "G_1") (pintype "passive"))
      (node (ref "U$1") (pin "51") (pinfunction "P0_3_51") (pintype "passive"))
    )
    (net (code "40") (name "P0.4") (class "Default")
      (node (ref "JP14") (pin "6") (pinfunction "6_6") (pintype "passive"))
      (node (ref "Q24") (pin "1") (pinfunction "G_1") (pintype "passive"))
      (node (ref "U$1") (pin "53") (pinfunction "P0_4_53") (pintype "passive"))
    )
    (net (code "41") (name "P0.5") (class "Default")
      (node (ref "JP11") (pin "4") (pinfunction "4_4") (pintype "passive"))
      (node (ref "JP14") (pin "7") (pinfunction "7_7") (pintype "passive"))
      (node (ref "U$1") (pin "54") (pinfunction "P0_5_54") (pintype "passive"))
      (node (ref "X6") (pin "2") (pinfunction "K_2") (pintype "passive"))
    )
    (net (code "42") (name "P0.6") (class "Default")
      (node (ref "JP11") (pin "5") (pinfunction "5_5") (pintype "passive"))
      (node (ref "JP14") (pin "8") (pinfunction "8_8") (pintype "passive"))
      (node (ref "U$1") (pin "55") (pinfunction "P0_6_55") (pintype "passive"))
      (node (ref "X6") (pin "1") (pinfunction "K_1") (pintype "passive"))
    )
    (net (code "43") (name "P0.7") (class "Default")
      (node (ref "JP11") (pin "6") (pinfunction "6_6") (pintype "passive"))
      (node (ref "JP14") (pin "9") (pinfunction "9_9") (pintype "passive"))
      (node (ref "U$1") (pin "56") (pinfunction "P0_7_56") (pintype "passive"))
      (node (ref "X7") (pin "5") (pinfunction "K_5") (pintype "passive"))
    )
    (net (code "44") (name "P1.0") (class "Default")
      (node (ref "JP13") (pin "1") (pinfunction "1_1") (pintype "passive"))
      (node (ref "Q11") (pin "1") (pinfunction "G_1") (pintype "passive"))
      (node (ref "U$1") (pin "38") (pinfunction "P12_0_I2C1_SCL_38") (pintype "passive"))
    )
    (net (code "45") (name "P1.1") (class "Default")
      (node (ref "JP13") (pin "2") (pinfunction "2_2") (pintype "passive"))
      (node (ref "Q23") (pin "1") (pinfunction "G_1") (pintype "passive"))
      (node (ref "U$1") (pin "39") (pinfunction "P12_1_I2C1_SDA_39") (pintype "passive"))
    )
    (net (code "46") (name "P1.2") (class "Default")
      (node (ref "JP12") (pin "5") (pinfunction "5_5") (pintype "passive"))
      (node (ref "JP13") (pin "3") (pinfunction "3_3") (pintype "passive"))
      (node (ref "U$1") (pin "46") (pinfunction "P12_2_46") (pintype "passive"))
      (node (ref "X2") (pin "1") (pinfunction "K_1") (pintype "passive"))
    )
    (net (code "47") (name "P1.3") (class "Default")
      (node (ref "JP12") (pin "6") (pinfunction "6_6") (pintype "passive"))
      (node (ref "JP13") (pin "4") (pinfunction "4_4") (pintype "passive"))
      (node (ref "U$1") (pin "47") (pinfunction "P12_3_47") (pintype "passive"))
      (node (ref "X3") (pin "5") (pinfunction "K_5") (pintype "passive"))
    )
    (net (code "48") (name "P1.4") (class "Default")
      (node (ref "JP13") (pin "5") (pinfunction "5_5") (pintype "passive"))
      (node (ref "Q19") (pin "1") (pinfunction "G_1") (pintype "passive"))
      (node (ref "U$1") (pin "3") (pinfunction "P12_4_I2C0_SCL_3") (pintype "passive"))
    )
    (net (code "49") (name "P1.5") (class "Default")
      (node (ref "JP12") (pin "9") (pinfunction "9_9") (pintype "passive"))
      (node (ref "JP13") (pin "6") (pinfunction "6_6") (pintype "passive"))
      (node (ref "U$1") (pin "4") (pinfunction "P12_5_I2C0_SDA_4") (pintype "passive"))
      (node (ref "X3") (pin "2") (pinfunction "K_2") (pintype "passive"))
    )
    (net (code "50") (name "P1.6") (class "Default")
      (node (ref "JP12") (pin "10") (pinfunction "10_10") (pintype "passive"))
      (node (ref "JP13") (pin "7") (pinfunction "7_7") (pintype "passive"))
      (node (ref "U$1") (pin "20") (pinfunction "P12_6_20") (pintype "passive"))
      (node (ref "X3") (pin "1") (pinfunction "K_1") (pintype "passive"))
    )
    (net (code "51") (name "P1.7") (class "Default")
      (node (ref "JP12") (pin "11") (pinfunction "11_11") (pintype "passive"))
      (node (ref "JP13") (pin "8") (pinfunction "8_8") (pintype "passive"))
      (node (ref "U$1") (pin "21") (pinfunction "P12_7_21") (pintype "passive"))
      (node (ref "X4") (pin "5") (pinfunction "K_5") (pintype "passive"))
    )
    (net (code "52") (name "P2.0") (class "Default")
      (node (ref "JP14") (pin "20") (pinfunction "20_20") (pintype "passive"))
      (node (ref "LED2") (pin "A") (pinfunction "A_A") (pintype "passive"))
      (node (ref "U$1") (pin "62") (pinfunction "P2_0_62") (pintype "passive"))
    )
    (net (code "53") (name "P2.1") (class "Default")
      (node (ref "JP11") (pin "19") (pinfunction "19_19") (pintype "passive"))
      (node (ref "JP14") (pin "19") (pinfunction "19_19") (pintype "passive"))
      (node (ref "U$1") (pin "63") (pinfunction "P2_1_63") (pintype "passive"))
      (node (ref "X9") (pin "2") (pinfunction "K_2") (pintype "passive"))
    )
    (net (code "54") (name "P2.2") (class "Default")
      (node (ref "JP11") (pin "18") (pinfunction "18_18") (pintype "passive"))
      (node (ref "JP14") (pin "18") (pinfunction "18_18") (pintype "passive"))
      (node (ref "U$1") (pin "64") (pinfunction "P2_2_64") (pintype "passive"))
      (node (ref "X9") (pin "3") (pinfunction "K_3") (pintype "passive"))
    )
    (net (code "55") (name "P2.3") (class "Default")
      (node (ref "JP11") (pin "17") (pinfunction "17_17") (pintype "passive"))
      (node (ref "JP14") (pin "17") (pinfunction "17_17") (pintype "passive"))
      (node (ref "U$1") (pin "65") (pinfunction "P2_3_65") (pintype "passive"))
      (node (ref "X9") (pin "4") (pinfunction "K_4") (pintype "passive"))
    )
    (net (code "56") (name "P2.4") (class "Default")
      (node (ref "JP11") (pin "15") (pinfunction "15_15") (pintype "passive"))
      (node (ref "JP14") (pin "16") (pinfunction "16_16") (pintype "passive"))
      (node (ref "U$1") (pin "66") (pinfunction "P2_4_66") (pintype "passive"))
      (node (ref "X8") (pin "1") (pinfunction "K_1") (pintype "passive"))
    )
    (net (code "57") (name "P2.5") (class "Default")
      (node (ref "JP11") (pin "14") (pinfunction "14_14") (pintype "passive"))
      (node (ref "JP14") (pin "15") (pinfunction "15_15") (pintype "passive"))
      (node (ref "U$1") (pin "68") (pinfunction "P2_5_68") (pintype "passive"))
      (node (ref "X8") (pin "2") (pinfunction "K_2") (pintype "passive"))
    )
    (net (code "58") (name "P2.6") (class "Default")
      (node (ref "JP11") (pin "13") (pinfunction "13_13") (pintype "passive"))
      (node (ref "JP14") (pin "14") (pinfunction "14_14") (pintype "passive"))
      (node (ref "U$1") (pin "1") (pinfunction "P2_6_1") (pintype "passive"))
      (node (ref "X8") (pin "3") (pinfunction "K_3") (pintype "passive"))
    )
    (net (code "59") (name "P2.7") (class "Default")
      (node (ref "JP11") (pin "11") (pinfunction "11_11") (pintype "passive"))
      (node (ref "JP14") (pin "13") (pinfunction "13_13") (pintype "passive"))
      (node (ref "U$1") (pin "2") (pinfunction "P2_7_2") (pintype "passive"))
      (node (ref "X8") (pin "5") (pinfunction "K_5") (pintype "passive"))
    )
    (net (code "60") (name "P3.0") (class "Default")
      (node (ref "JP12") (pin "14") (pinfunction "14_14") (pintype "passive"))
      (node (ref "JP13") (pin "10") (pinfunction "10_10") (pintype "passive"))
      (node (ref "U$1") (pin "29") (pinfunction "P3_0_29") (pintype "passive"))
      (node (ref "X4") (pin "2") (pinfunction "K_2") (pintype "passive"))
    )
    (net (code "61") (name "P3.1") (class "Default")
      (node (ref "JP12") (pin "15") (pinfunction "15_15") (pintype "passive"))
      (node (ref "JP13") (pin "11") (pinfunction "11_11") (pintype "passive"))
      (node (ref "U$1") (pin "30") (pinfunction "P3_1_30") (pintype "passive"))
      (node (ref "X4") (pin "1") (pinfunction "K_1") (pintype "passive"))
    )
    (net (code "62") (name "P3.2") (class "Default")
      (node (ref "JP12") (pin "17") (pinfunction "17_17") (pintype "passive"))
      (node (ref "JP13") (pin "12") (pinfunction "12_12") (pintype "passive"))
      (node (ref "U$1") (pin "31") (pinfunction "P3_2_31") (pintype "passive"))
      (node (ref "X5") (pin "4") (pinfunction "K_4") (pintype "passive"))
    )
    (net (code "63") (name "P3.3") (class "Default")
      (node (ref "JP13") (pin "13") (pinfunction "13_13") (pintype "passive"))
      (node (ref "Q21") (pin "1") (pinfunction "G_1") (pintype "passive"))
      (node (ref "U$1") (pin "32") (pinfunction "P3_3_32") (pintype "passive"))
    )
    (net (code "64") (name "P3.4") (class "Default")
      (node (ref "JP12") (pin "19") (pinfunction "19_19") (pintype "passive"))
      (node (ref "JP13") (pin "14") (pinfunction "14_14") (pintype "passive"))
      (node (ref "U$1") (pin "33") (pinfunction "P3_4_33") (pintype "passive"))
      (node (ref "X5") (pin "2") (pinfunction "K_2") (pintype "passive"))
    )
    (net (code "65") (name "P3.5") (class "Default")
      (node (ref "JP12") (pin "20") (pinfunction "20_20") (pintype "passive"))
      (node (ref "JP13") (pin "15") (pinfunction "15_15") (pintype "passive"))
      (node (ref "U$1") (pin "34") (pinfunction "P3_5_34") (pintype "passive"))
      (node (ref "X5") (pin "1") (pinfunction "K_1") (pintype "passive"))
    )
    (net (code "66") (name "P3.6") (class "Default")
      (node (ref "J4") (pin "3") (pinfunction "1_3") (pintype "passive"))
      (node (ref "JP13") (pin "16") (pinfunction "16_16") (pintype "passive"))
      (node (ref "Q1") (pin "3") (pinfunction "D_3") (pintype "passive"))
      (node (ref "R15") (pin "1") (pinfunction "1_1") (pintype "passive"))
      (node (ref "U$1") (pin "36") (pinfunction "P3_6_36") (pintype "passive"))
    )
    (net (code "67") (name "P3.7") (class "Default")
      (node (ref "J4") (pin "2") (pinfunction "1_2") (pintype "passive"))
      (node (ref "JP13") (pin "17") (pinfunction "17_17") (pintype "passive"))
      (node (ref "Q2") (pin "3") (pinfunction "D_3") (pintype "passive"))
      (node (ref "R13") (pin "1") (pinfunction "1_1") (pintype "passive"))
      (node (ref "U$1") (pin "37") (pinfunction "P3_7_37") (pintype "passive"))
    )
    (net (code "68") (name "PWRMON") (class "Default")
      (node (ref "IC1") (pin "49") (pinfunction "PWRMON_49") (pintype "bidirectional"))
      (node (ref "JP8") (pin "3") (pinfunction "3_3") (pintype "passive"))
    )
    (net (code "69") (name "RESET") (class "Default")
      (node (ref "JP12") (pin "12") (pinfunction "12_12") (pintype "passive"))
      (node (ref "JP13") (pin "9") (pinfunction "9_9") (pintype "passive"))
      (node (ref "U$1") (pin "19") (pinfunction "P1_7_19") (pintype "passive"))
      (node (ref "X4") (pin "4") (pinfunction "K_4") (pintype "passive"))
    )
    (net (code "70") (name "RXD") (class "Default")
      (node (ref "IC1") (pin "26") (pinfunction "C104/RXD_26") (pintype "output"))
      (node (ref "Q2") (pin "2") (pinfunction "S_2") (pintype "passive"))
      (node (ref "R2") (pin "1") (pinfunction "1_1") (pintype "passive"))
    )
    (net (code "71") (name "SEL3V3") (class "Default")
      (node (ref "JP9") (pin "1") (pinfunction "1_1") (pintype "passive"))
      (node (ref "R17") (pin "1") (pinfunction "1_1") (pintype "passive"))
    )
    (net (code "72") (name "SENSE") (class "Default")
      (node (ref "IC2") (pin "2") (pinfunction "SENSE_2") (pintype "input"))
      (node (ref "JP9") (pin "2") (pinfunction "2_2") (pintype "passive"))
      (node (ref "R14") (pin "1") (pinfunction "1_1") (pintype "passive"))
      (node (ref "R16") (pin "2") (pinfunction "2_2") (pintype "passive"))
    )
    (net (code "73") (name "STAT_LED") (class "Default")
      (node (ref "IC1") (pin "45") (pinfunction "STAT_LED_45") (pintype "output"))
      (node (ref "R5") (pin "2") (pinfunction "2_2") (pintype "passive"))
    )
    (net (code "74") (name "SWDCK") (class "Default")
      (node (ref "Q3") (pin "4") (pinfunction "4_4") (pintype "bidirectional"))
      (node (ref "U$1") (pin "12") (pinfunction "P1_1_TCK_12") (pintype "passive"))
      (node (ref "X10") (pin "2") (pinfunction "S_2") (pintype "passive"))
    )
    (net (code "75") (name "SWDIO") (class "Default")
      (node (ref "Q3") (pin "2") (pinfunction "2_2") (pintype "bidirectional"))
      (node (ref "U$1") (pin "11") (pinfunction "P1_0_TMS_11") (pintype "passive"))
      (node (ref "X10") (pin "1") (pinfunction "S_1") (pintype "passive"))
    )
    (net (code "76") (name "SWV") (class "Default")
      (node (ref "Q3") (pin "6") (pinfunction "6_6") (pintype "bidirectional"))
      (node (ref "U$1") (pin "14") (pinfunction "P1_3_TDO_14") (pintype "passive"))
    )
    (net (code "77") (name "TDI") (class "Default")
      (node (ref "Q3") (pin "8") (pinfunction "8_8") (pintype "bidirectional"))
      (node (ref "U$1") (pin "15") (pinfunction "P1_4_TDI_15") (pintype "passive"))
    )
    (net (code "78") (name "TLOGIC") (class "Default")
      (node (ref "JP8") (pin "2") (pinfunction "2_2") (pintype "passive"))
      (node (ref "Q1") (pin "1") (pinfunction "G_1") (pintype "passive"))
      (node (ref "Q2") (pin "1") (pinfunction "G_1") (pintype "passive"))
      (node (ref "R1") (pin "2") (pinfunction "2_2") (pintype "passive"))
      (node (ref "R2") (pin "2") (pinfunction "2_2") (pintype "passive"))
    )
    (net (code "79") (name "TXD") (class "Default")
      (node (ref "IC1") (pin "25") (pinfunction "C103/TXD_25") (pintype "input"))
      (node (ref "Q1") (pin "2") (pinfunction "S_2") (pintype "passive"))
      (node (ref "R1") (pin "1") (pinfunction "1_1") (pintype "passive"))
    )
    (net (code "80") (name "T_ONOFF") (class "Default")
      (node (ref "IC1") (pin "53") (pinfunction "ON/OFF_53") (pintype "input"))
      (node (ref "JP7") (pin "2") (pinfunction "2_2") (pintype "passive"))
    )
    (net (code "81") (name "T_RESET") (class "Default")
      (node (ref "IC1") (pin "54") (pinfunction "RESET_54") (pintype "input"))
      (node (ref "JP6") (pin "2") (pinfunction "2_2") (pintype "passive"))
    )
    (net (code "82") (name "VAUX") (class "Default")
      (node (ref "IC1") (pin "50") (pinfunction "VAUX1_50") (pintype "passive"))
      (node (ref "JP8") (pin "1") (pinfunction "1_1") (pintype "passive"))
      (node (ref "R12") (pin "2") (pinfunction "2_2") (pintype "passive"))
    )
    (net (code "83") (name "VBAT") (class "Default")
      (node (ref "D4") (pin "A") (pinfunction "A_A") (pintype "passive"))
      (node (ref "Q10") (pin "2") (pinfunction "S_2") (pintype "passive"))
      (node (ref "Q12") (pin "2") (pinfunction "S_2") (pintype "passive"))
      (node (ref "Q22") (pin "2") (pinfunction "S_2") (pintype "passive"))
      (node (ref "R18") (pin "2") (pinfunction "2_2") (pintype "passive"))
      (node (ref "R19") (pin "2") (pinfunction "2_2") (pintype "passive"))
      (node (ref "R26") (pin "2") (pinfunction "2_2") (pintype "passive"))
      (node (ref "X1") (pin "1") (pinfunction "K_1") (pintype "passive"))
    )
    (net (code "84") (name "VBAT1") (class "Default")
      (node (ref "JP11") (pin "1") (pinfunction "1_1") (pintype "passive"))
      (node (ref "JP12") (pin "1") (pinfunction "1_1") (pintype "passive"))
      (node (ref "Q10") (pin "3") (pinfunction "D_3") (pintype "passive"))
      (node (ref "X2") (pin "5") (pinfunction "K_5") (pintype "passive"))
      (node (ref "X6") (pin "5") (pinfunction "K_5") (pintype "passive"))
    )
    (net (code "85") (name "VBAT2") (class "Default")
      (node (ref "JP12") (pin "2") (pinfunction "2_2") (pintype "passive"))
      (node (ref "Q12") (pin "3") (pinfunction "D_3") (pintype "passive"))
      (node (ref "X2") (pin "4") (pinfunction "K_4") (pintype "passive"))
    )
    (net (code "86") (name "VCCD") (class "Default")
      (node (ref "C17") (pin "1") (pinfunction "1_1") (pintype "passive"))
      (node (ref "U$1") (pin "26") (pinfunction "VCCD_26") (pintype "passive"))
      (node (ref "U$1") (pin "57") (pinfunction "VCCD_57") (pintype "passive"))
    )
    (net (code "87") (name "VDD") (class "Default")
      (node (ref "C10") (pin "1") (pinfunction "1_1") (pintype "passive"))
      (node (ref "C11") (pin "1") (pinfunction "1_1") (pintype "passive"))
      (node (ref "C12") (pin "1") (pinfunction "1_1") (pintype "passive"))
      (node (ref "C13") (pin "1") (pinfunction "1_1") (pintype "passive"))
      (node (ref "C14") (pin "1") (pinfunction "1_1") (pintype "passive"))
      (node (ref "C15") (pin "1") (pinfunction "1_1") (pintype "passive"))
      (node (ref "C16") (pin "1") (pinfunction "1_1") (pintype "passive"))
      (node (ref "C18") (pin "1") (pinfunction "1_1") (pintype "passive"))
      (node (ref "C2") (pin "A") (pinfunction "+_A") (pintype "passive"))
      (node (ref "C3") (pin "1") (pinfunction "1_1") (pintype "passive"))
      (node (ref "C7") (pin "1") (pinfunction "1_1") (pintype "passive"))
      (node (ref "C8") (pin "1") (pinfunction "1_1") (pintype "passive"))
      (node (ref "IC2") (pin "1") (pinfunction "OUT_1") (pintype "passive"))
      (node (ref "JP14") (pin "1") (pinfunction "1_1") (pintype "passive"))
      (node (ref "JP3") (pin "3") (pinfunction "3_3") (pintype "passive"))
      (node (ref "Q14") (pin "2") (pinfunction "S_2") (pintype "passive"))
      (node (ref "Q16") (pin "2") (pinfunction "S_2") (pintype "passive"))
      (node (ref "Q18") (pin "2") (pinfunction "S_2") (pintype "passive"))
      (node (ref "Q20") (pin "2") (pinfunction "S_2") (pintype "passive"))
      (node (ref "Q24") (pin "2") (pinfunction "S_2") (pintype "passive"))
      (node (ref "R14") (pin "2") (pinfunction "2_2") (pintype "passive"))
      (node (ref "R17") (pin "2") (pinfunction "2_2") (pintype "passive"))
      (node (ref "R20") (pin "2") (pinfunction "2_2") (pintype "passive"))
      (node (ref "R21") (pin "2") (pinfunction "2_2") (pintype "passive"))
      (node (ref "R22") (pin "2") (pinfunction "2_2") (pintype "passive"))
      (node (ref "R23") (pin "2") (pinfunction "2_2") (pintype "passive"))
      (node (ref "U$1") (pin "17") (pinfunction "VDDIO1_17") (pintype "passive"))
      (node (ref "U$1") (pin "24") (pinfunction "VDDD_24") (pintype "passive"))
      (node (ref "U$1") (pin "35") (pinfunction "VDDIO3_35") (pintype "passive"))
      (node (ref "U$1") (pin "44") (pinfunction "VDDA_44") (pintype "passive"))
      (node (ref "U$1") (pin "52") (pinfunction "VDDIO0_52") (pintype "passive"))
      (node (ref "U$1") (pin "59") (pinfunction "VDDD_59") (pintype "passive"))
      (node (ref "U$1") (pin "67") (pinfunction "VDDIO2_67") (pintype "passive"))
      (node (ref "X10") (pin "5") (pinfunction "S_5") (pintype "passive"))
    )
    (net (code "88") (name "VDD1") (class "Default")
      (node (ref "JP11") (pin "2") (pinfunction "2_2") (pintype "passive"))
      (node (ref "JP12") (pin "3") (pinfunction "3_3") (pintype "passive"))
      (node (ref "Q14") (pin "3") (pinfunction "D_3") (pintype "passive"))
      (node (ref "X2") (pin "3") (pinfunction "K_3") (pintype "passive"))
      (node (ref "X6") (pin "4") (pinfunction "K_4") (pintype "passive"))
    )
    (net (code "89") (name "VDD2") (class "Default")
      (node (ref "JP12") (pin "4") (pinfunction "4_4") (pintype "passive"))
      (node (ref "Q16") (pin "3") (pinfunction "D_3") (pintype "passive"))
      (node (ref "X2") (pin "2") (pinfunction "K_2") (pintype "passive"))
    )
    (net (code "90") (name "VDD3") (class "Default")
      (node (ref "JP12") (pin "7") (pinfunction "7_7") (pintype "passive"))
      (node (ref "Q18") (pin "3") (pinfunction "D_3") (pintype "passive"))
      (node (ref "X3") (pin "4") (pinfunction "K_4") (pintype "passive"))
    )
    (net (code "91") (name "VDD4") (class "Default")
      (node (ref "JP12") (pin "18") (pinfunction "18_18") (pintype "passive"))
      (node (ref "Q20") (pin "3") (pinfunction "D_3") (pintype "passive"))
      (node (ref "X5") (pin "3") (pinfunction "K_3") (pintype "passive"))
    )
    (net (code "92") (name "VDDD") (class "Default")
      (node (ref "C30") (pin "1") (pinfunction "1_1") (pintype "passive"))
      (node (ref "Q3") (pin "1") (pinfunction "1_1") (pintype "bidirectional"))
    )
    (net (code "93") (name "VTARG") (class "Default")
      (node (ref "J4") (pin "1") (pinfunction "1_1") (pintype "passive"))
      (node (ref "JP4") (pin "2") (pinfunction "2_2") (pintype "passive"))
      (node (ref "R13") (pin "2") (pinfunction "2_2") (pintype "passive"))
      (node (ref "R15") (pin "2") (pinfunction "2_2") (pintype "passive"))
    )
    (net (code "94") (name "V_TELIT") (class "Default")
      (node (ref "D2") (pin "A") (pinfunction "A_A") (pintype "passive"))
      (node (ref "J2") (pin "1") (pinfunction "1_1") (pintype "passive"))
      (node (ref "JP1") (pin "3") (pinfunction "3_3") (pintype "passive"))
      (node (ref "JP4") (pin "1") (pinfunction "1_1") (pintype "passive"))
      (node (ref "JP5") (pin "1") (pinfunction "1_1") (pintype "passive"))
      (node (ref "Q24") (pin "3") (pinfunction "D_3") (pintype "passive"))
    )
    (net (code "95") (name "unconnected-(IC1-ADC_IN1-Pad37)") (class "Default")
      (node (ref "IC1") (pin "37") (pinfunction "ADC_IN1_37") (pintype "input"))
    )
    (net (code "96") (name "unconnected-(IC1-ADC_IN2-Pad38)") (class "Default")
      (node (ref "IC1") (pin "38") (pinfunction "ADC_IN2_38") (pintype "input"))
    )
    (net (code "97") (name "unconnected-(IC1-ADC_IN3-Pad39)") (class "Default")
      (node (ref "IC1") (pin "39") (pinfunction "ADC_IN3_39") (pintype "input"))
    )
    (net (code "98") (name "unconnected-(IC1-AXE-Pad8)") (class "Default")
      (node (ref "IC1") (pin "8") (pinfunction "AXE_8") (pintype "input"))
    )
    (net (code "99") (name "unconnected-(IC1-C105{slash}RTS-Pad31)") (class "Default")
      (node (ref "IC1") (pin "31") (pinfunction "C105/RTS_31") (pintype "input"))
    )
    (net (code "100") (name "unconnected-(IC1-C106{slash}CTS-Pad28)") (class "Default")
      (node (ref "IC1") (pin "28") (pinfunction "C106/CTS_28") (pintype "output"))
    )
    (net (code "101") (name "unconnected-(IC1-C107{slash}DSR-Pad27)") (class "Default")
      (node (ref "IC1") (pin "27") (pinfunction "C107/DSR_27") (pintype "output"))
    )
    (net (code "102") (name "unconnected-(IC1-C109{slash}DCD-Pad32)") (class "Default")
      (node (ref "IC1") (pin "32") (pinfunction "C109/DCD_32") (pintype "output"))
    )
    (net (code "103") (name "unconnected-(IC1-C125{slash}RING-Pad30)") (class "Default")
      (node (ref "IC1") (pin "30") (pinfunction "C125/RING_30") (pintype "output"))
    )
    (net (code "104") (name "unconnected-(IC1-CAM_SCL-Pad35)") (class "Default")
      (node (ref "IC1") (pin "35") (pinfunction "CAM_SCL_35") (pintype "bidirectional"))
    )
    (net (code "105") (name "unconnected-(IC1-CAM_SDA-Pad36)") (class "Default")
      (node (ref "IC1") (pin "36") (pinfunction "CAM_SDA_36") (pintype "bidirectional"))
    )
    (net (code "106") (name "unconnected-(IC1-DAC_OUT-Pad40)") (class "Default")
      (node (ref "IC1") (pin "40") (pinfunction "DAC_OUT_40") (pintype "output"))
    )
    (net (code "107") (name "unconnected-(IC1-EAR_HF+-Pad9)") (class "Default")
      (node (ref "IC1") (pin "9") (pinfunction "EAR_HF+_9") (pintype "passive"))
    )
    (net (code "108") (name "unconnected-(IC1-EAR_HF--Pad10)") (class "Default")
      (node (ref "IC1") (pin "10") (pinfunction "EAR_HF-_10") (pintype "passive"))
    )
    (net (code "109") (name "unconnected-(IC1-EAR_MT+-Pad11)") (class "Default")
      (node (ref "IC1") (pin "11") (pinfunction "EAR_MT+_11") (pintype "passive"))
    )
    (net (code "110") (name "unconnected-(IC1-EAR_MT--Pad12)") (class "Default")
      (node (ref "IC1") (pin "12") (pinfunction "EAR_MT-_12") (pintype "passive"))
    )
    (net (code "111") (name "unconnected-(IC1-GPIO1-Pad70)") (class "Default")
      (node (ref "IC1") (pin "70") (pinfunction "GPIO1_70") (pintype "bidirectional"))
    )
    (net (code "112") (name "unconnected-(IC1-GPIO2-Pad74)") (class "Default")
      (node (ref "IC1") (pin "74") (pinfunction "GPIO2_74") (pintype "bidirectional"))
    )
    (net (code "113") (name "unconnected-(IC1-GPIO3-Pad66)") (class "Default")
      (node (ref "IC1") (pin "66") (pinfunction "GPIO3_66") (pintype "bidirectional"))
    )
    (net (code "114") (name "unconnected-(IC1-GPIO4-Pad59)") (class "Default")
      (node (ref "IC1") (pin "59") (pinfunction "GPIO4_59") (pintype "bidirectional"))
    )
    (net (code "115") (name "unconnected-(IC1-GPIO5-Pad78)") (class "Default")
      (node (ref "IC1") (pin "78") (pinfunction "GPIO5_78") (pintype "bidirectional"))
    )
    (net (code "116") (name "unconnected-(IC1-GPIO6-Pad68)") (class "Default")
      (node (ref "IC1") (pin "68") (pinfunction "GPIO6_68") (pintype "bidirectional"))
    )
    (net (code "117") (name "unconnected-(IC1-GPIO7-Pad73)") (class "Default")
      (node (ref "IC1") (pin "73") (pinfunction "GPIO7_73") (pintype "bidirectional"))
    )
    (net (code "118") (name "unconnected-(IC1-GPIO8-Pad67)") (class "Default")
      (node (ref "IC1") (pin "67") (pinfunction "GPIO8_67") (pintype "bidirectional"))
    )
    (net (code "119") (name "unconnected-(IC1-GPIO9-Pad76)") (class "Default")
      (node (ref "IC1") (pin "76") (pinfunction "GPIO9_76") (pintype "bidirectional"))
    )
    (net (code "120") (name "unconnected-(IC1-GPIO10-Pad63)") (class "Default")
      (node (ref "IC1") (pin "63") (pinfunction "GPIO10_63") (pintype "bidirectional"))
    )
    (net (code "121") (name "unconnected-(IC1-GPIO11-Pad57)") (class "Default")
      (node (ref "IC1") (pin "57") (pinfunction "GPIO11_57") (pintype "bidirectional"))
    )
    (net (code "122") (name "unconnected-(IC1-GPIO12-Pad62)") (class "Default")
      (node (ref "IC1") (pin "62") (pinfunction "GPIO12_62") (pintype "bidirectional"))
    )
    (net (code "123") (name "unconnected-(IC1-GPIO13-Pad77)") (class "Default")
      (node (ref "IC1") (pin "77") (pinfunction "GPIO13_77") (pintype "bidirectional"))
    )
    (net (code "124") (name "unconnected-(IC1-GPIO14-Pad60)") (class "Default")
      (node (ref "IC1") (pin "60") (pinfunction "GPIO14_60") (pintype "bidirectional"))
    )
    (net (code "125") (name "unconnected-(IC1-GPIO15-Pad61)") (class "Default")
      (node (ref "IC1") (pin "61") (pinfunction "GPIO15_61") (pintype "bidirectional"))
    )
    (net (code "126") (name "unconnected-(IC1-GPIO16-Pad75)") (class "Default")
      (node (ref "IC1") (pin "75") (pinfunction "GPIO16_75") (pintype "bidirectional"))
    )
    (net (code "127") (name "unconnected-(IC1-GPIO17-Pad71)") (class "Default")
      (node (ref "IC1") (pin "71") (pinfunction "GPIO17_71") (pintype "bidirectional"))
    )
    (net (code "128") (name "unconnected-(IC1-GPIO18-Pad65)") (class "Default")
      (node (ref "IC1") (pin "65") (pinfunction "GPIO18_65") (pintype "bidirectional"))
    )
    (net (code "129") (name "unconnected-(IC1-GPIO19-Pad56)") (class "Default")
      (node (ref "IC1") (pin "56") (pinfunction "GPIO19_56") (pintype "bidirectional"))
    )
    (net (code "130") (name "unconnected-(IC1-GPIO20-Pad58)") (class "Default")
      (node (ref "IC1") (pin "58") (pinfunction "GPIO20_58") (pintype "bidirectional"))
    )
    (net (code "131") (name "unconnected-(IC1-GPIO21-Pad72)") (class "Default")
      (node (ref "IC1") (pin "72") (pinfunction "GPIO21_72") (pintype "bidirectional"))
    )
    (net (code "132") (name "unconnected-(IC1-GPIO22-Pad64)") (class "Default")
      (node (ref "IC1") (pin "64") (pinfunction "GPIO22_64") (pintype "bidirectional"))
    )
    (net (code "133") (name "unconnected-(IC1-GPIO23-Pad69)") (class "Default")
      (node (ref "IC1") (pin "69") (pinfunction "GPIO23_69") (pintype "bidirectional"))
    )
    (net (code "134") (name "unconnected-(IC1-MIC_HF+-Pad13)") (class "Default")
      (node (ref "IC1") (pin "13") (pinfunction "MIC_HF+_13") (pintype "passive"))
    )
    (net (code "135") (name "unconnected-(IC1-MIC_HF--Pad14)") (class "Default")
      (node (ref "IC1") (pin "14") (pinfunction "MIC_HF-_14") (pintype "passive"))
    )
    (net (code "136") (name "unconnected-(IC1-MIC_MT+-Pad15)") (class "Default")
      (node (ref "IC1") (pin "15") (pinfunction "MIC_MT+_15") (pintype "passive"))
    )
    (net (code "137") (name "unconnected-(IC1-MIC_MT--Pad16)") (class "Default")
      (node (ref "IC1") (pin "16") (pinfunction "MIC_MT-_16") (pintype "passive"))
    )
    (net (code "138") (name "unconnected-(IC1-MON1_CAM-Pad44)") (class "Default")
      (node (ref "IC1") (pin "44") (pinfunction "MON1_CAM_44") (pintype "bidirectional"))
    )
    (net (code "139") (name "unconnected-(IC1-NC17-Pad17)") (class "Default")
      (node (ref "IC1") (pin "17") (pinfunction "NC17_17") (pintype "no_connect"))
    )
    (net (code "140") (name "unconnected-(IC1-NC33-Pad33)") (class "Default")
      (node (ref "IC1") (pin "33") (pinfunction "NC33_33") (pintype "no_connect"))
    )
    (net (code "141") (name "unconnected-(IC1-NC34-Pad34)") (class "Default")
      (node (ref "IC1") (pin "34") (pinfunction "NC34_34") (pintype "no_connect"))
    )
    (net (code "142") (name "unconnected-(IC1-NC41-Pad41)") (class "Default")
      (node (ref "IC1") (pin "41") (pinfunction "NC41_41") (pintype "no_connect"))
    )
    (net (code "143") (name "unconnected-(IC1-NC42-Pad42)") (class "Default")
      (node (ref "IC1") (pin "42") (pinfunction "NC42_42") (pintype "no_connect"))
    )
    (net (code "144") (name "unconnected-(IC1-NC43-Pad43)") (class "Default")
      (node (ref "IC1") (pin "43") (pinfunction "NC43_43") (pintype "no_connect"))
    )
    (net (code "145") (name "unconnected-(IC1-NC47-Pad47)") (class "Default")
      (node (ref "IC1") (pin "47") (pinfunction "NC47_47") (pintype "no_connect"))
    )
    (net (code "146") (name "unconnected-(IC1-NC48-Pad48)") (class "Default")
      (node (ref "IC1") (pin "48") (pinfunction "NC48_48") (pintype "no_connect"))
    )
    (net (code "147") (name "unconnected-(IC1-NC79-Pad79)") (class "Default")
      (node (ref "IC1") (pin "79") (pinfunction "NC79_79") (pintype "no_connect"))
    )
    (net (code "148") (name "unconnected-(IC1-NC80-Pad80)") (class "Default")
      (node (ref "IC1") (pin "80") (pinfunction "NC80_80") (pintype "no_connect"))
    )
    (net (code "149") (name "unconnected-(IC1-RX_TRACE-Pad23)") (class "Default")
      (node (ref "IC1") (pin "23") (pinfunction "RX_TRACE_23") (pintype "passive"))
    )
    (net (code "150") (name "unconnected-(IC1-SIMCLK-Pad22)") (class "Default")
      (node (ref "IC1") (pin "22") (pinfunction "SIMCLK_22") (pintype "output"))
    )
    (net (code "151") (name "unconnected-(IC1-SIMIN-Pad21)") (class "Default")
      (node (ref "IC1") (pin "21") (pinfunction "SIMIN_21") (pintype "input"))
    )
    (net (code "152") (name "unconnected-(IC1-SIMIO-Pad20)") (class "Default")
      (node (ref "IC1") (pin "20") (pinfunction "SIMIO_20") (pintype "bidirectional"))
    )
    (net (code "153") (name "unconnected-(IC1-SIMRST-Pad19)") (class "Default")
      (node (ref "IC1") (pin "19") (pinfunction "SIMRST_19") (pintype "output"))
    )
    (net (code "154") (name "unconnected-(IC1-SIMVCC-Pad18)") (class "Default")
      (node (ref "IC1") (pin "18") (pinfunction "SIMVCC_18") (pintype "passive"))
    )
    (net (code "155") (name "unconnected-(IC1-TX_TRACE-Pad24)") (class "Default")
      (node (ref "IC1") (pin "24") (pinfunction "TX_TRACE_24") (pintype "passive"))
    )
    (net (code "156") (name "unconnected-(IC1-VRTC-Pad55)") (class "Default")
      (node (ref "IC1") (pin "55") (pinfunction "VRTC_55") (pintype "passive"))
    )
    (net (code "157") (name "unconnected-(JP9-Pad3)") (class "Default")
      (node (ref "JP9") (pin "3") (pinfunction "3_3") (pintype "passive"))
    )
    (net (code "158") (name "unconnected-(U$1A-IND-Pad6)") (class "Default")
      (node (ref "U$1") (pin "6") (pinfunction "IND_6") (pintype "passive"))
    )
    (net (code "159") (name "unconnected-(U$1A-P1_2-Pad13)") (class "Default")
      (node (ref "U$1") (pin "13") (pinfunction "P1_2_13") (pintype "passive"))
    )
    (net (code "160") (name "unconnected-(U$1A-P1_5_NTRST-Pad16)") (class "Default")
      (node (ref "U$1") (pin "16") (pinfunction "P1_5_NTRST_16") (pintype "passive"))
    )
    (net (code "161") (name "unconnected-(U$1A-P15_2_KXO-Pad40)") (class "Default")
      (node (ref "U$1") (pin "40") (pinfunction "P15_2_KXO_40") (pintype "passive"))
    )
    (net (code "162") (name "unconnected-(U$1A-P15_3_KXI-Pad41)") (class "Default")
      (node (ref "U$1") (pin "41") (pinfunction "P15_3_KXI_41") (pintype "passive"))
    )
    (net (code "163") (name "unconnected-(U$1A-P15_6_DP-Pad22)") (class "Default")
      (node (ref "U$1") (pin "22") (pinfunction "P15_6_DP_22") (pintype "passive"))
    )
    (net (code "164") (name "unconnected-(U$1A-P15_7_DM-Pad23)") (class "Default")
      (node (ref "U$1") (pin "23") (pinfunction "P15_7_DM_23") (pintype "passive"))
    )
    (net (code "165") (name "~{EA}") (class "Default")
      (node (ref "JP11") (pin "7") (pinfunction "7_7") (pintype "passive"))
      (node (ref "JP14") (pin "10") (pinfunction "10_10") (pintype "passive"))
      (node (ref "U$1") (pin "18") (pinfunction "P1_6_18") (pintype "passive"))
      (node (ref "X7") (pin "4") (pinfunction "K_4") (pintype "passive"))
    )
    (net (code "166") (name "~{PSEN}") (class "Default")
      (node (ref "JP11") (pin "10") (pinfunction "10_10") (pintype "passive"))
      (node (ref "JP14") (pin "12") (pinfunction "12_12") (pintype "passive"))
      (node (ref "U$1") (pin "61") (pinfunction "P15_5_61") (pintype "passive"))
      (node (ref "X7") (pin "1") (pinfunction "K_1") (pintype "passive"))
    )
    (net (code "167") (name "~{XRES}") (class "Default")
      (node (ref "Q3") (pin "10") (pinfunction "10_10") (pintype "bidirectional"))
      (node (ref "U$1") (pin "10") (pinfunction "XRES_10") (pintype "passive"))
      (node (ref "X10") (pin "3") (pinfunction "S_3") (pintype "passive"))
      (node (ref "XRES") (pin "1") (pinfunction "1_1") (pintype "passive"))
      (node (ref "XRES") (pin "2") (pinfunction "2_2") (pintype "passive"))
    )
  )
)
